# Relay_fused_CKT.net
KiCad netlist of a schematic drawn in Altium Designer
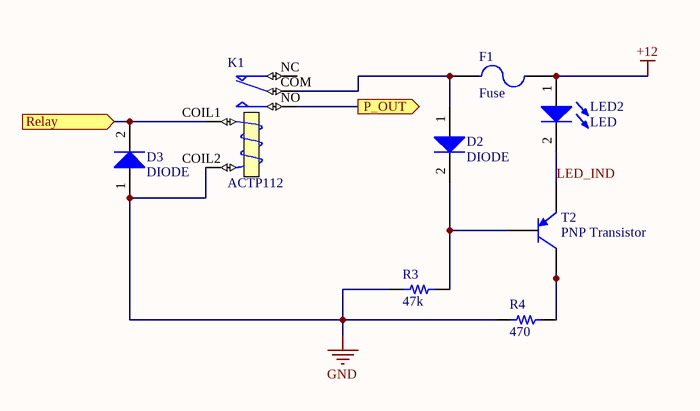
[diagram p0: Relay fused CKT.SchDoc]

(export (version "E")
  (design (tool "Eeschema 10.0.6"))
  (components
    (comp (ref "D2")
      (value "DIODE")
      (footprint "SOD123F")
      (description "Diode Super Barrier 40V 1A Surface Mount SOD-123F")
      (fields (field (name "POWER") "40V") (field (name "MFRPARTNO") "1N5819HW1-7-F"))
      (libsource (lib "Altium-Lib") (part "DIODE"))
    )
    (comp (ref "D3")
      (value "DIODE")
      (footprint "SOD123F")
      (description "Diode Super Barrier 40V 1A Surface Mount SOD-123F")
      (fields (field (name "POWER") "40V") (field (name "MFRPARTNO") "1N5819HW1-7-F"))
      (libsource (lib "Altium-Lib") (part "DIODE"))
    )
    (comp (ref "F1")
      (value "Fuse")
      (footprint "3568-MiniFuseHolder")
      (libsource (lib "Altium-Lib") (part "Fuse"))
    )
    (comp (ref "K1")
      (value "ACTP112")
      (footprint "ACTP112")
      (fields (field (name "PUBLISHER") "Altium Limited"))
      (libsource (lib "Altium-Lib") (part "ACTP112"))
    )
    (comp (ref "LED2") (value "LED") (footprint "0805_LED") (libsource (lib "Altium-Lib") (part "LED")))
    (comp (ref "R3")
      (value "47k")
      (footprint "RES 0805/2012")
      (fields
        (field (name "TOLERANCE") "1%")
        (field (name "POWER") "1/10W")
        (field (name "Comment") "Resistor 47k 0805 1/10W 1%")
        (field (name "CREATED_BY") "Nick Mah")
      )
      (libsource (lib "Altium-Lib") (part "Resistor"))
    )
    (comp (ref "R4")
      (value "470")
      (footprint "RES 0805/2012")
      (fields
        (field (name "TOLERANCE") "1%")
        (field (name "POWER") "1/10W")
        (field (name "Comment") "Resistor 470 0805 1/10W 1%")
        (field (name "CREATED_BY") "Nick Mah")
      )
      (libsource (lib "Altium-Lib") (part "Resistor"))
    )
    (comp (ref "T2")
      (value "PNP Transistor")
      (footprint "SOT23-3")
      (fields (field (name "MFRPARTNO") "MMBT4403WT1G") (field (name "CREATED_BY") "Angel"))
      (libsource (lib "Altium-Lib") (part "PNP Transistor"))
    )
  )
  (nets
    (net (code "1") (name "+12") (class "Default")
      (node (ref "F1") (pin "2") (pinfunction "2_2") (pintype "passive"))
      (node (ref "LED2") (pin "1") (pinfunction "A_1") (pintype "passive"))
    )
    (net (code "2") (name "/LED_IND") (class "Default")
      (node (ref "LED2") (pin "2") (pinfunction "K_2") (pintype "passive"))
      (node (ref "T2") (pin "2") (pinfunction "E_2") (pintype "passive"))
    )
    (net (code "3") (name "/P_OUT") (class "Default")
      (node (ref "K1") (pin "NO") (pinfunction "NO_NO") (pintype "bidirectional"))
    )
    (net (code "4") (name "/Relay") (class "Default")
      (node (ref "D3") (pin "2") (pinfunction "K_2") (pintype "passive"))
      (node (ref "K1") (pin "COIL1") (pinfunction "T1_COIL1") (pintype "bidirectional"))
    )
    (net (code "5") (name "GND") (class "Default")
      (node (ref "D3") (pin "1") (pinfunction "A_1") (pintype "passive"))
      (node (ref "K1") (pin "COIL2") (pinfunction "T2_COIL2") (pintype "bidirectional"))
      (node (ref "R3") (pin "2") (pinfunction "2_2") (pintype "passive"))
      (node (ref "R4") (pin "2") (pinfunction "2_2") (pintype "passive"))
    )
    (net (code "6") (name "Net-(D2-A)") (class "Default")
      (node (ref "D2") (pin "1") (pinfunction "A_1") (pintype "passive"))
      (node (ref "F1") (pin "1") (pinfunction "1_1") (pintype "passive"))
      (node (ref "K1") (pin "COM") (pinfunction "COM_COM") (pintype "bidirectional"))
    )
    (net (code "7") (name "Net-(D2-K)") (class "Default")
      (node (ref "D2") (pin "2") (pinfunction "K_2") (pintype "passive"))
      (node (ref "R3") (pin "1") (pinfunction "1_1") (pintype "passive"))
      (node (ref "T2") (pin "1") (pinfunction "B_1") (pintype "passive"))
    )
    (net (code "8") (name "Net-(T2-C)") (class "Default")
      (node (ref "R4") (pin "1") (pinfunction "1_1") (pintype "passive"))
      (node (ref "T2") (pin "3") (pinfunction "C_3") (pintype "passive"))
    )
    (net (code "9") (name "unconnected-(K1-PadNC)") (class "Default")
      (node (ref "K1") (pin "NC") (pinfunction "NC_NC") (pintype "bidirectional"))
    )
  )
)
